# OS-MPS_Preamp_V2_OnlyINA.net
KiCad netlist of a schematic drawn in EAGLE
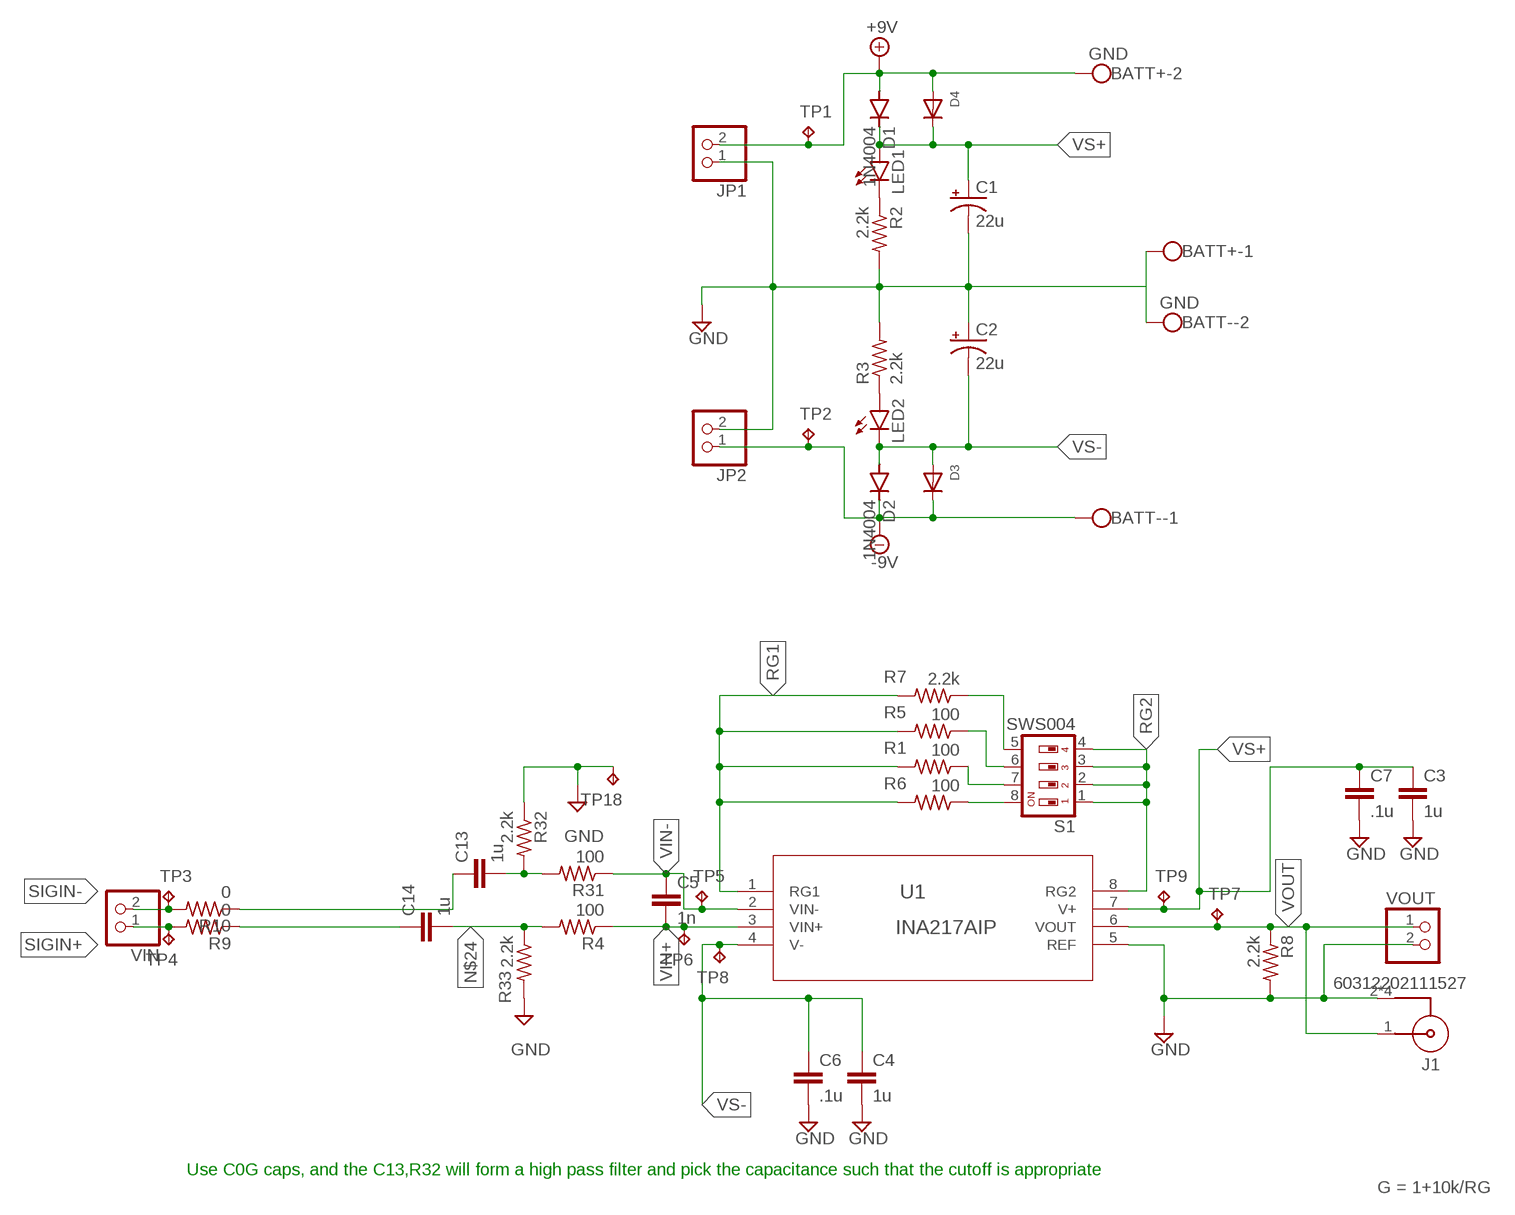
[diagram p0: schematic, sheet 1]

(export (version "E")
  (design (tool "Eeschema 10.0.6"))
  (components
    (comp (ref "BATT+")
      (value "GND")
      (footprint "eagle-import:W237-102")
      (fields (field (name "MPN") "237-102"))
      (libsource (lib "eagle-import") (part "W237-102"))
    )
    (comp (ref "BATT-")
      (value "GND")
      (footprint "eagle-import:W237-102")
      (fields (field (name "MPN") "237-102"))
      (libsource (lib "eagle-import") (part "W237-102"))
    )
    (comp (ref "C1")
      (value "22u")
      (footprint "eagle-import:TT2D6")
      (libsource (lib "eagle-import") (part "CPOL-USTT2D6"))
    )
    (comp (ref "C2")
      (value "22u")
      (footprint "eagle-import:TT2D6")
      (libsource (lib "eagle-import") (part "CPOL-USTT2D6"))
    )
    (comp (ref "C3")
      (value "1u")
      (footprint "eagle-import:C1206")
      (libsource (lib "eagle-import") (part "C-EUC1206"))
    )
    (comp (ref "C4")
      (value "1u")
      (footprint "eagle-import:C1206")
      (libsource (lib "eagle-import") (part "C-EUC1206"))
    )
    (comp (ref "C5")
      (value "1n")
      (footprint "eagle-import:C1206")
      (libsource (lib "eagle-import") (part "C-EUC1206"))
    )
    (comp (ref "C6")
      (value ".1u")
      (footprint "eagle-import:C1206")
      (libsource (lib "eagle-import") (part "C-EUC1206"))
    )
    (comp (ref "C7")
      (value ".1u")
      (footprint "eagle-import:C1206")
      (libsource (lib "eagle-import") (part "C-EUC1206"))
    )
    (comp (ref "C13")
      (value "1u")
      (footprint "eagle-import:C1206")
      (libsource (lib "eagle-import") (part "C-EUC1206"))
    )
    (comp (ref "C14")
      (value "1u")
      (footprint "eagle-import:C1206")
      (libsource (lib "eagle-import") (part "C-EUC1206"))
    )
    (comp (ref "D1")
      (value "1N4004")
      (footprint "eagle-import:DO41-10")
      (libsource (lib "eagle-import") (part "1N4004"))
    )
    (comp (ref "D2")
      (value "1N4004")
      (footprint "eagle-import:DO41-10")
      (libsource (lib "eagle-import") (part "1N4004"))
    )
    (comp (ref "D3")
      (value "DIODESOD-123")
      (footprint "eagle-import:SOD-123")
      (libsource (lib "eagle-import") (part "DIODESOD-123"))
    )
    (comp (ref "D4")
      (value "DIODESOD-123")
      (footprint "eagle-import:SOD-123")
      (libsource (lib "eagle-import") (part "DIODESOD-123"))
    )
    (comp (ref "J1")
      (value "60312202111527")
      (footprint "eagle-import:60312202111527")
      (libsource (lib "eagle-import") (part "60312202111527"))
    )
    (comp (ref "JP1")
      (value "PINHD-1X2")
      (footprint "eagle-import:1X02")
      (libsource (lib "eagle-import") (part "PINHD-1X2"))
    )
    (comp (ref "JP2")
      (value "PINHD-1X2")
      (footprint "eagle-import:1X02")
      (libsource (lib "eagle-import") (part "PINHD-1X2"))
    )
    (comp (ref "LED1")
      (value "LEDSML0805")
      (footprint "eagle-import:SML0805")
      (libsource (lib "eagle-import") (part "LEDSML0805"))
    )
    (comp (ref "LED2")
      (value "LEDSML0805")
      (footprint "eagle-import:SML0805")
      (libsource (lib "eagle-import") (part "LEDSML0805"))
    )
    (comp (ref "R1")
      (value "100")
      (footprint "eagle-import:R0805")
      (libsource (lib "eagle-import") (part "R-US_R0805"))
    )
    (comp (ref "R2")
      (value "2.2k")
      (footprint "eagle-import:R0805")
      (libsource (lib "eagle-import") (part "R-US_R0805"))
    )
    (comp (ref "R3")
      (value "2.2k")
      (footprint "eagle-import:R0805")
      (libsource (lib "eagle-import") (part "R-US_R0805"))
    )
    (comp (ref "R4")
      (value "100")
      (footprint "eagle-import:R0805")
      (libsource (lib "eagle-import") (part "R-US_R0805"))
    )
    (comp (ref "R5")
      (value "100")
      (footprint "eagle-import:R0805")
      (libsource (lib "eagle-import") (part "R-US_R0805"))
    )
    (comp (ref "R6")
      (value "100")
      (footprint "eagle-import:R0805")
      (libsource (lib "eagle-import") (part "R-US_R0805"))
    )
    (comp (ref "R7")
      (value "2.2k")
      (footprint "eagle-import:R0805")
      (libsource (lib "eagle-import") (part "R-US_R0805"))
    )
    (comp (ref "R8")
      (value "2.2k")
      (footprint "eagle-import:R0805")
      (libsource (lib "eagle-import") (part "R-US_R0805"))
    )
    (comp (ref "R9")
      (value "0")
      (footprint "eagle-import:R0805")
      (libsource (lib "eagle-import") (part "R-US_R0805"))
    )
    (comp (ref "R10")
      (value "0")
      (footprint "eagle-import:R0805")
      (libsource (lib "eagle-import") (part "R-US_R0805"))
    )
    (comp (ref "R31")
      (value "100")
      (footprint "eagle-import:R0805")
      (libsource (lib "eagle-import") (part "R-US_R0805"))
    )
    (comp (ref "R32")
      (value "2.2k")
      (footprint "eagle-import:R0805")
      (libsource (lib "eagle-import") (part "R-US_R0805"))
    )
    (comp (ref "R33")
      (value "2.2k")
      (footprint "eagle-import:R0805")
      (libsource (lib "eagle-import") (part "R-US_R0805"))
    )
    (comp (ref "S1")
      (value "SWS004")
      (footprint "eagle-import:SMS-004")
      (libsource (lib "eagle-import") (part "SWS004"))
    )
    (comp (ref "TP1")
      (value "TPB2,54")
      (footprint "eagle-import:B2,54")
      (libsource (lib "eagle-import") (part "TPB2,54"))
    )
    (comp (ref "TP2")
      (value "TPB2,54")
      (footprint "eagle-import:B2,54")
      (libsource (lib "eagle-import") (part "TPB2,54"))
    )
    (comp (ref "TP3")
      (value "TPTP20SQ")
      (footprint "eagle-import:TP20SQ")
      (libsource (lib "eagle-import") (part "TPTP20SQ"))
    )
    (comp (ref "TP4")
      (value "TPTP20SQ")
      (footprint "eagle-import:TP20SQ")
      (libsource (lib "eagle-import") (part "TPTP20SQ"))
    )
    (comp (ref "TP5")
      (value "TPTP20SQ")
      (footprint "eagle-import:TP20SQ")
      (libsource (lib "eagle-import") (part "TPTP20SQ"))
    )
    (comp (ref "TP6")
      (value "TPTP20SQ")
      (footprint "eagle-import:TP20SQ")
      (libsource (lib "eagle-import") (part "TPTP20SQ"))
    )
    (comp (ref "TP7")
      (value "TPTP20SQ")
      (footprint "eagle-import:TP20SQ")
      (libsource (lib "eagle-import") (part "TPTP20SQ"))
    )
    (comp (ref "TP8")
      (value "TPTP20SQ")
      (footprint "eagle-import:TP20SQ")
      (libsource (lib "eagle-import") (part "TPTP20SQ"))
    )
    (comp (ref "TP9")
      (value "TPTP20SQ")
      (footprint "eagle-import:TP20SQ")
      (libsource (lib "eagle-import") (part "TPTP20SQ"))
    )
    (comp (ref "TP18")
      (value "TPTP20SQ")
      (footprint "eagle-import:TP20SQ")
      (libsource (lib "eagle-import") (part "TPTP20SQ"))
    )
    (comp (ref "U1")
      (value "INA217AIP")
      (footprint "eagle-import:P8")
      (fields (field (name "GENERIC_PART_NUMBER") "INA217") (field (name "MANUFACTURER") "Texas Instruments"))
      (libsource (lib "eagle-import") (part "INA217AIP"))
    )
    (comp (ref "VIN")
      (value "PINHD-1X2")
      (footprint "eagle-import:1X02")
      (libsource (lib "eagle-import") (part "PINHD-1X2"))
    )
    (comp (ref "VOUT")
      (value "PINHD-1X2")
      (footprint "eagle-import:1X02")
      (libsource (lib "eagle-import") (part "PINHD-1X2"))
    )
  )
  (nets
    (net (code "1") (name "+9V") (class "Default")
      (node (ref "BATT+") (pin "2") (pinfunction "KL_2") (pintype "passive"))
      (node (ref "D1") (pin "A") (pinfunction "A_A") (pintype "passive"))
      (node (ref "D4") (pin "A") (pinfunction "A_A") (pintype "passive"))
      (node (ref "JP1") (pin "2") (pinfunction "2_2") (pintype "passive"))
      (node (ref "TP1") (pin "TP") (pinfunction "TP_TP") (pintype "input"))
    )
    (net (code "2") (name "-9V") (class "Default")
      (node (ref "BATT-") (pin "1") (pinfunction "KL_1") (pintype "passive"))
      (node (ref "D2") (pin "C") (pinfunction "C_C") (pintype "passive"))
      (node (ref "D3") (pin "C") (pinfunction "C_C") (pintype "passive"))
      (node (ref "JP2") (pin "1") (pinfunction "1_1") (pintype "passive"))
      (node (ref "TP2") (pin "TP") (pinfunction "TP_TP") (pintype "input"))
    )
    (net (code "3") (name "GND") (class "Default")
      (node (ref "BATT+") (pin "1") (pinfunction "KL_1") (pintype "passive"))
      (node (ref "BATT-") (pin "2") (pinfunction "KL_2") (pintype "passive"))
      (node (ref "C1") (pin "-") (pinfunction "-_-") (pintype "passive"))
      (node (ref "C2") (pin "+") (pinfunction "+_+") (pintype "passive"))
      (node (ref "C3") (pin "2") (pinfunction "2_2") (pintype "passive"))
      (node (ref "C4") (pin "2") (pinfunction "2_2") (pintype "passive"))
      (node (ref "C6") (pin "2") (pinfunction "2_2") (pintype "passive"))
      (node (ref "C7") (pin "2") (pinfunction "2_2") (pintype "passive"))
      (node (ref "J1") (pin "2") (pinfunction "2_2") (pintype "passive"))
      (node (ref "J1") (pin "3") (pinfunction "2_3") (pintype "passive"))
      (node (ref "J1") (pin "4") (pinfunction "2_4") (pintype "passive"))
      (node (ref "J1") (pin "5") (pinfunction "2_5") (pintype "passive"))
      (node (ref "JP1") (pin "1") (pinfunction "1_1") (pintype "passive"))
      (node (ref "JP2") (pin "2") (pinfunction "2_2") (pintype "passive"))
      (node (ref "R2") (pin "2") (pinfunction "2_2") (pintype "passive"))
      (node (ref "R3") (pin "2") (pinfunction "2_2") (pintype "passive"))
      (node (ref "R32") (pin "1") (pinfunction "1_1") (pintype "passive"))
      (node (ref "R33") (pin "2") (pinfunction "2_2") (pintype "passive"))
      (node (ref "R8") (pin "2") (pinfunction "2_2") (pintype "passive"))
      (node (ref "TP18") (pin "TP") (pinfunction "TP_TP") (pintype "input"))
      (node (ref "U1") (pin "5") (pinfunction "REF_5") (pintype "passive"))
      (node (ref "VOUT") (pin "2") (pinfunction "2_2") (pintype "passive"))
    )
    (net (code "4") (name "N$24") (class "Default")
      (node (ref "C14") (pin "2") (pinfunction "2_2") (pintype "passive"))
      (node (ref "R33") (pin "1") (pinfunction "1_1") (pintype "passive"))
      (node (ref "R4") (pin "2") (pinfunction "2_2") (pintype "passive"))
    )
    (net (code "5") (name "Net-(C13-Pad1)") (class "Default")
      (node (ref "C13") (pin "1") (pinfunction "1_1") (pintype "passive"))
      (node (ref "R10") (pin "1") (pinfunction "1_1") (pintype "passive"))
    )
    (net (code "6") (name "Net-(C13-Pad2)") (class "Default")
      (node (ref "C13") (pin "2") (pinfunction "2_2") (pintype "passive"))
      (node (ref "R31") (pin "2") (pinfunction "2_2") (pintype "passive"))
      (node (ref "R32") (pin "2") (pinfunction "2_2") (pintype "passive"))
    )
    (net (code "7") (name "Net-(C14-Pad1)") (class "Default")
      (node (ref "C14") (pin "1") (pinfunction "1_1") (pintype "passive"))
      (node (ref "R9") (pin "1") (pinfunction "1_1") (pintype "passive"))
    )
    (net (code "8") (name "Net-(LED1-PadC)") (class "Default")
      (node (ref "LED1") (pin "C") (pinfunction "C_C") (pintype "passive"))
      (node (ref "R2") (pin "1") (pinfunction "1_1") (pintype "passive"))
    )
    (net (code "9") (name "Net-(LED2-PadA)") (class "Default")
      (node (ref "LED2") (pin "A") (pinfunction "A_A") (pintype "passive"))
      (node (ref "R3") (pin "1") (pinfunction "1_1") (pintype "passive"))
    )
    (net (code "10") (name "Net-(R1-Pad1)") (class "Default")
      (node (ref "R1") (pin "1") (pinfunction "1_1") (pintype "passive"))
      (node (ref "S1") (pin "7") (pinfunction "7_7") (pintype "passive"))
    )
    (net (code "11") (name "Net-(R5-Pad1)") (class "Default")
      (node (ref "R5") (pin "1") (pinfunction "1_1") (pintype "passive"))
      (node (ref "S1") (pin "6") (pinfunction "6_6") (pintype "passive"))
    )
    (net (code "12") (name "Net-(R6-Pad1)") (class "Default")
      (node (ref "R6") (pin "1") (pinfunction "1_1") (pintype "passive"))
      (node (ref "S1") (pin "8") (pinfunction "8_8") (pintype "passive"))
    )
    (net (code "13") (name "Net-(R7-Pad1)") (class "Default")
      (node (ref "R7") (pin "1") (pinfunction "1_1") (pintype "passive"))
      (node (ref "S1") (pin "5") (pinfunction "5_5") (pintype "passive"))
    )
    (net (code "14") (name "RG1") (class "Default")
      (node (ref "R1") (pin "2") (pinfunction "2_2") (pintype "passive"))
      (node (ref "R5") (pin "2") (pinfunction "2_2") (pintype "passive"))
      (node (ref "R6") (pin "2") (pinfunction "2_2") (pintype "passive"))
      (node (ref "R7") (pin "2") (pinfunction "2_2") (pintype "passive"))
      (node (ref "U1") (pin "1") (pinfunction "RG1_1") (pintype "passive"))
    )
    (net (code "15") (name "RG2") (class "Default")
      (node (ref "S1") (pin "1") (pinfunction "1_1") (pintype "passive"))
      (node (ref "S1") (pin "2") (pinfunction "2_2") (pintype "passive"))
      (node (ref "S1") (pin "3") (pinfunction "3_3") (pintype "passive"))
      (node (ref "S1") (pin "4") (pinfunction "4_4") (pintype "passive"))
      (node (ref "U1") (pin "8") (pinfunction "RG2_8") (pintype "passive"))
    )
    (net (code "16") (name "SIGIN+") (class "Default")
      (node (ref "R9") (pin "2") (pinfunction "2_2") (pintype "passive"))
      (node (ref "TP4") (pin "TP") (pinfunction "TP_TP") (pintype "input"))
      (node (ref "VIN") (pin "1") (pinfunction "1_1") (pintype "passive"))
    )
    (net (code "17") (name "SIGIN-") (class "Default")
      (node (ref "R10") (pin "2") (pinfunction "2_2") (pintype "passive"))
      (node (ref "TP3") (pin "TP") (pinfunction "TP_TP") (pintype "input"))
      (node (ref "VIN") (pin "2") (pinfunction "2_2") (pintype "passive"))
    )
    (net (code "18") (name "VIN+") (class "Default")
      (node (ref "C5") (pin "2") (pinfunction "2_2") (pintype "passive"))
      (node (ref "R4") (pin "1") (pinfunction "1_1") (pintype "passive"))
      (node (ref "TP6") (pin "TP") (pinfunction "TP_TP") (pintype "input"))
      (node (ref "U1") (pin "3") (pinfunction "VIN+_3") (pintype "passive"))
    )
    (net (code "19") (name "VIN-") (class "Default")
      (node (ref "C5") (pin "1") (pinfunction "1_1") (pintype "passive"))
      (node (ref "R31") (pin "1") (pinfunction "1_1") (pintype "passive"))
      (node (ref "TP5") (pin "TP") (pinfunction "TP_TP") (pintype "input"))
      (node (ref "U1") (pin "2") (pinfunction "VIN-_2") (pintype "passive"))
    )
    (net (code "20") (name "VOUT") (class "Default")
      (node (ref "J1") (pin "1") (pinfunction "1_1") (pintype "passive"))
      (node (ref "R8") (pin "1") (pinfunction "1_1") (pintype "passive"))
      (node (ref "TP7") (pin "TP") (pinfunction "TP_TP") (pintype "input"))
      (node (ref "U1") (pin "6") (pinfunction "VOUT_6") (pintype "output"))
      (node (ref "VOUT") (pin "1") (pinfunction "1_1") (pintype "passive"))
    )
    (net (code "21") (name "VS+") (class "Default")
      (node (ref "C1") (pin "+") (pinfunction "+_+") (pintype "passive"))
      (node (ref "C3") (pin "1") (pinfunction "1_1") (pintype "passive"))
      (node (ref "C7") (pin "1") (pinfunction "1_1") (pintype "passive"))
      (node (ref "D1") (pin "C") (pinfunction "C_C") (pintype "passive"))
      (node (ref "D4") (pin "C") (pinfunction "C_C") (pintype "passive"))
      (node (ref "LED1") (pin "A") (pinfunction "A_A") (pintype "passive"))
      (node (ref "TP9") (pin "TP") (pinfunction "TP_TP") (pintype "input"))
      (node (ref "U1") (pin "7") (pinfunction "V+_7") (pintype "power_in"))
    )
    (net (code "22") (name "VS-") (class "Default")
      (node (ref "C2") (pin "-") (pinfunction "-_-") (pintype "passive"))
      (node (ref "C4") (pin "1") (pinfunction "1_1") (pintype "passive"))
      (node (ref "C6") (pin "1") (pinfunction "1_1") (pintype "passive"))
      (node (ref "D2") (pin "A") (pinfunction "A_A") (pintype "passive"))
      (node (ref "D3") (pin "A") (pinfunction "A_A") (pintype "passive"))
      (node (ref "LED2") (pin "C") (pinfunction "C_C") (pintype "passive"))
      (node (ref "TP8") (pin "TP") (pinfunction "TP_TP") (pintype "input"))
      (node (ref "U1") (pin "4") (pinfunction "V-_4") (pintype "power_in"))
    )
  )
)
